# the_ties.net
KiCad netlist of a schematic drawn in EasyEDA Pro
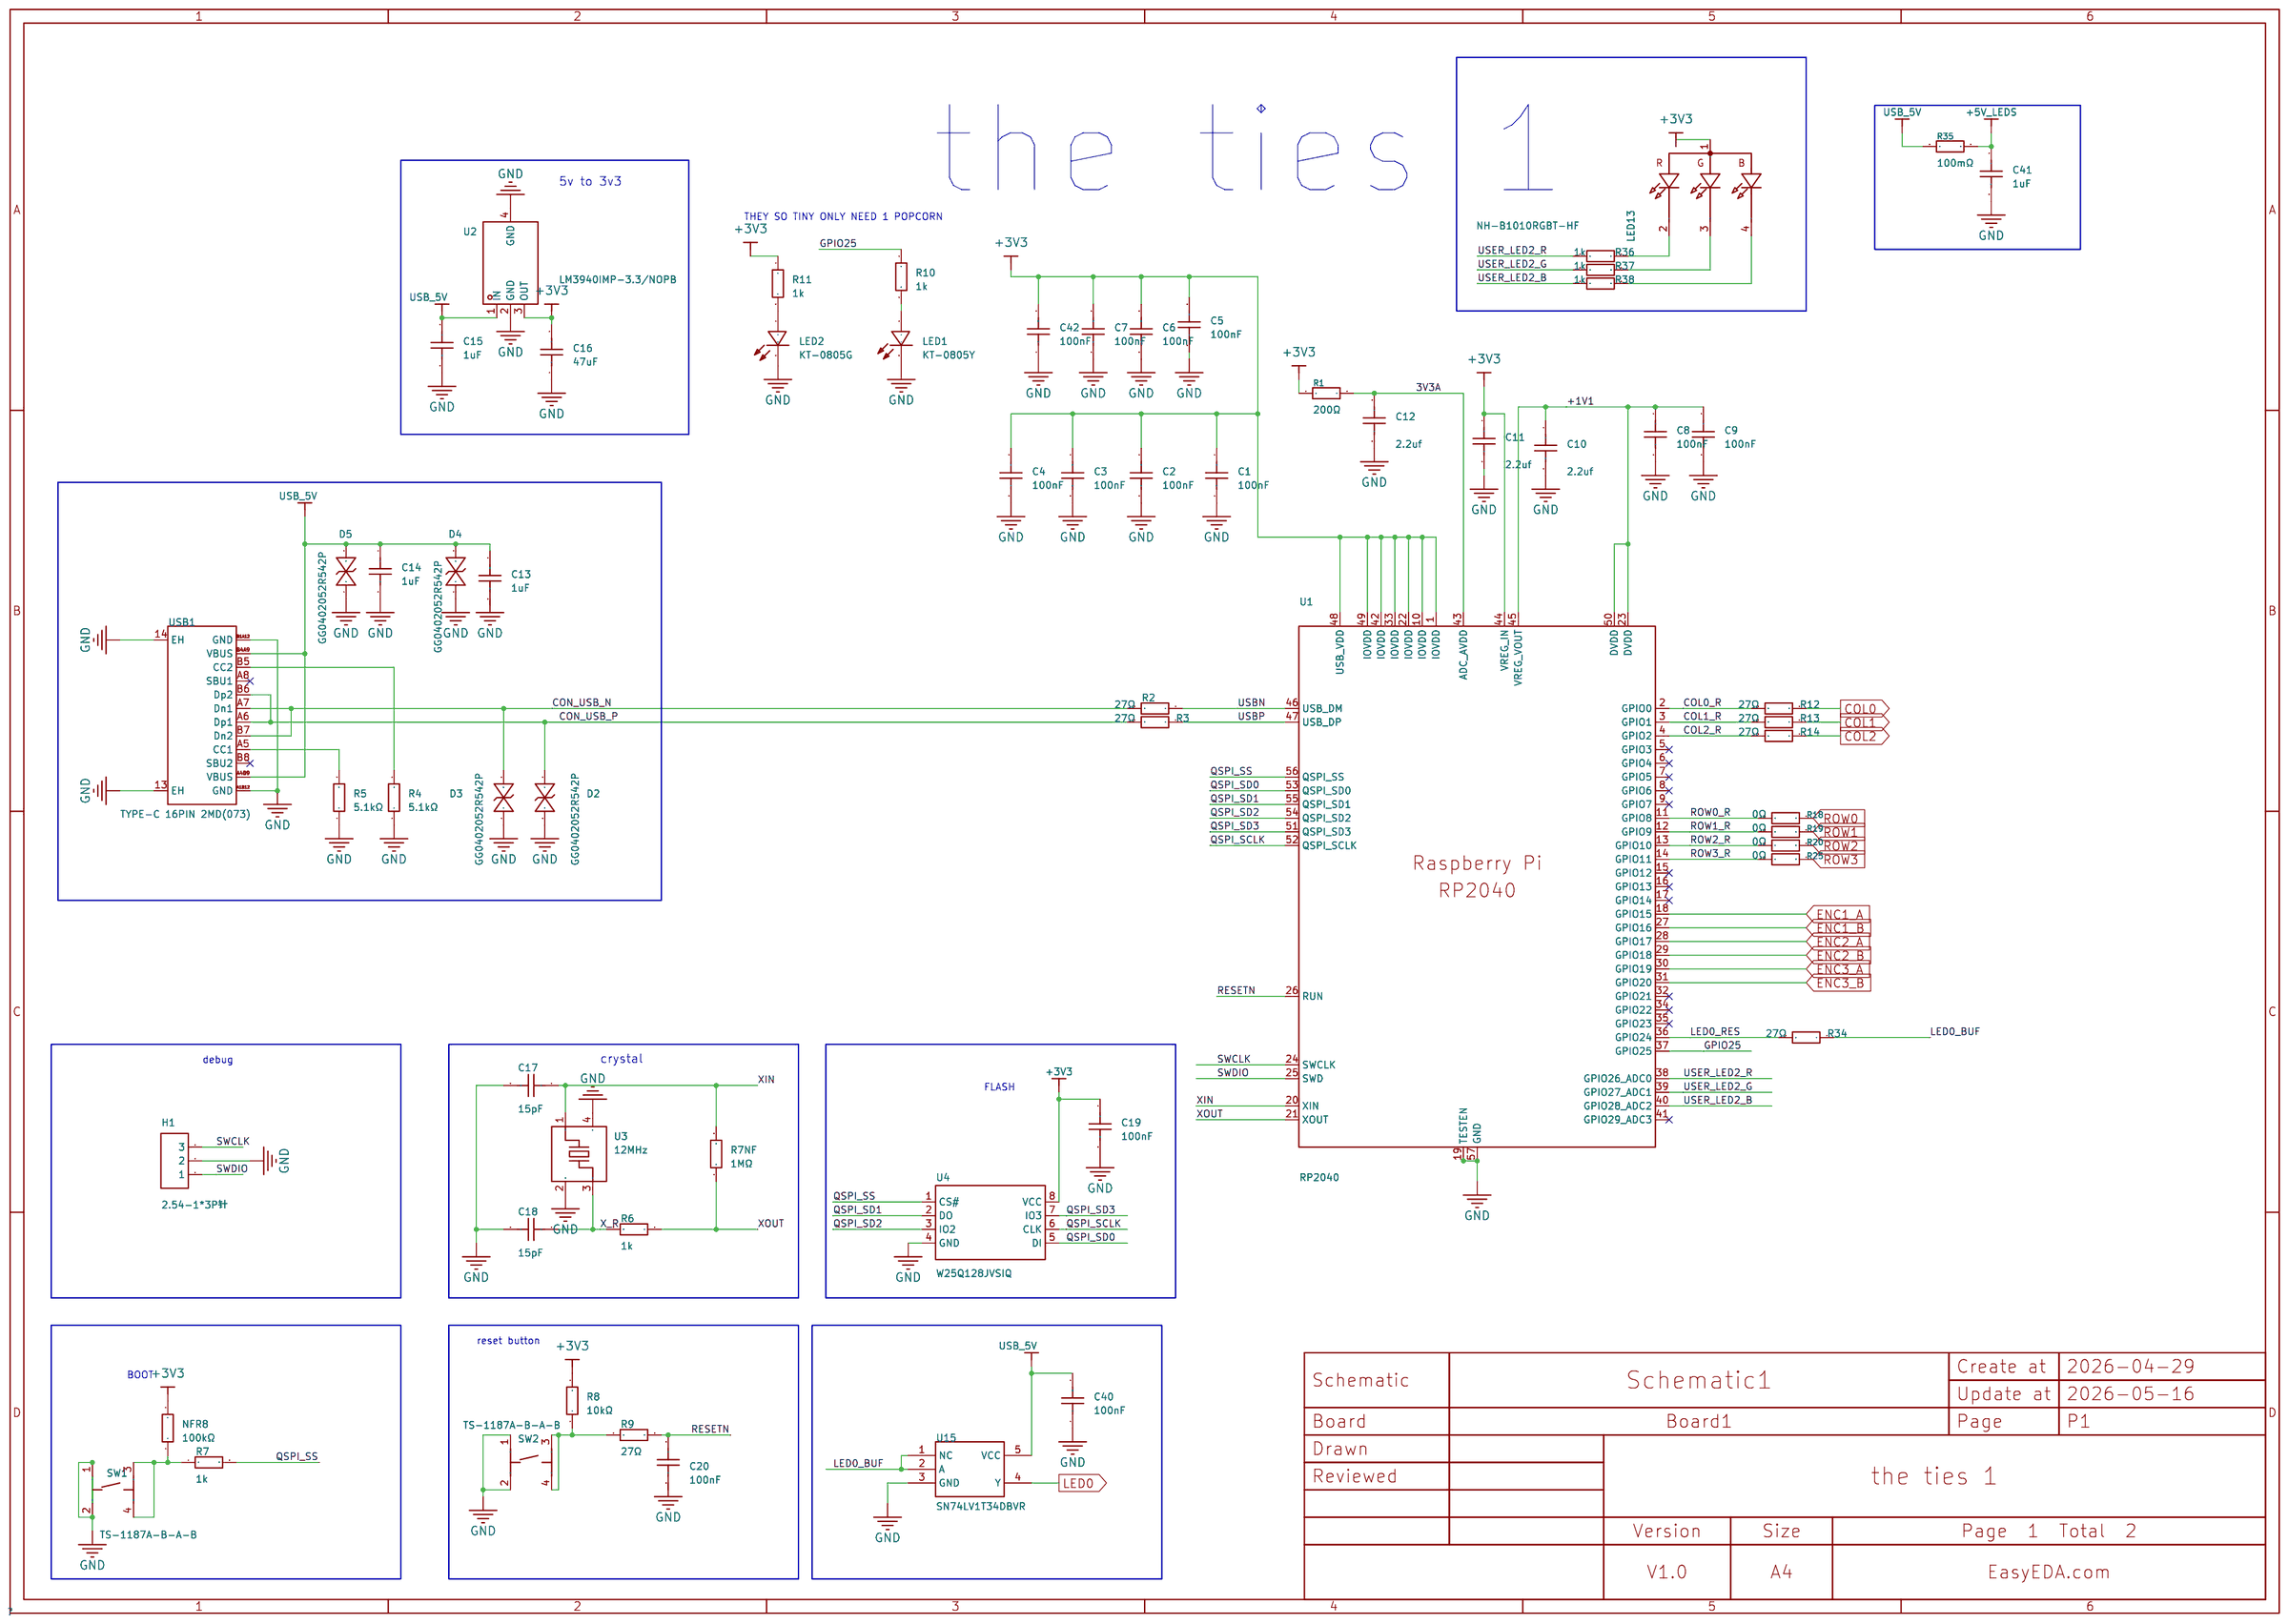
[diagram p0: P1]
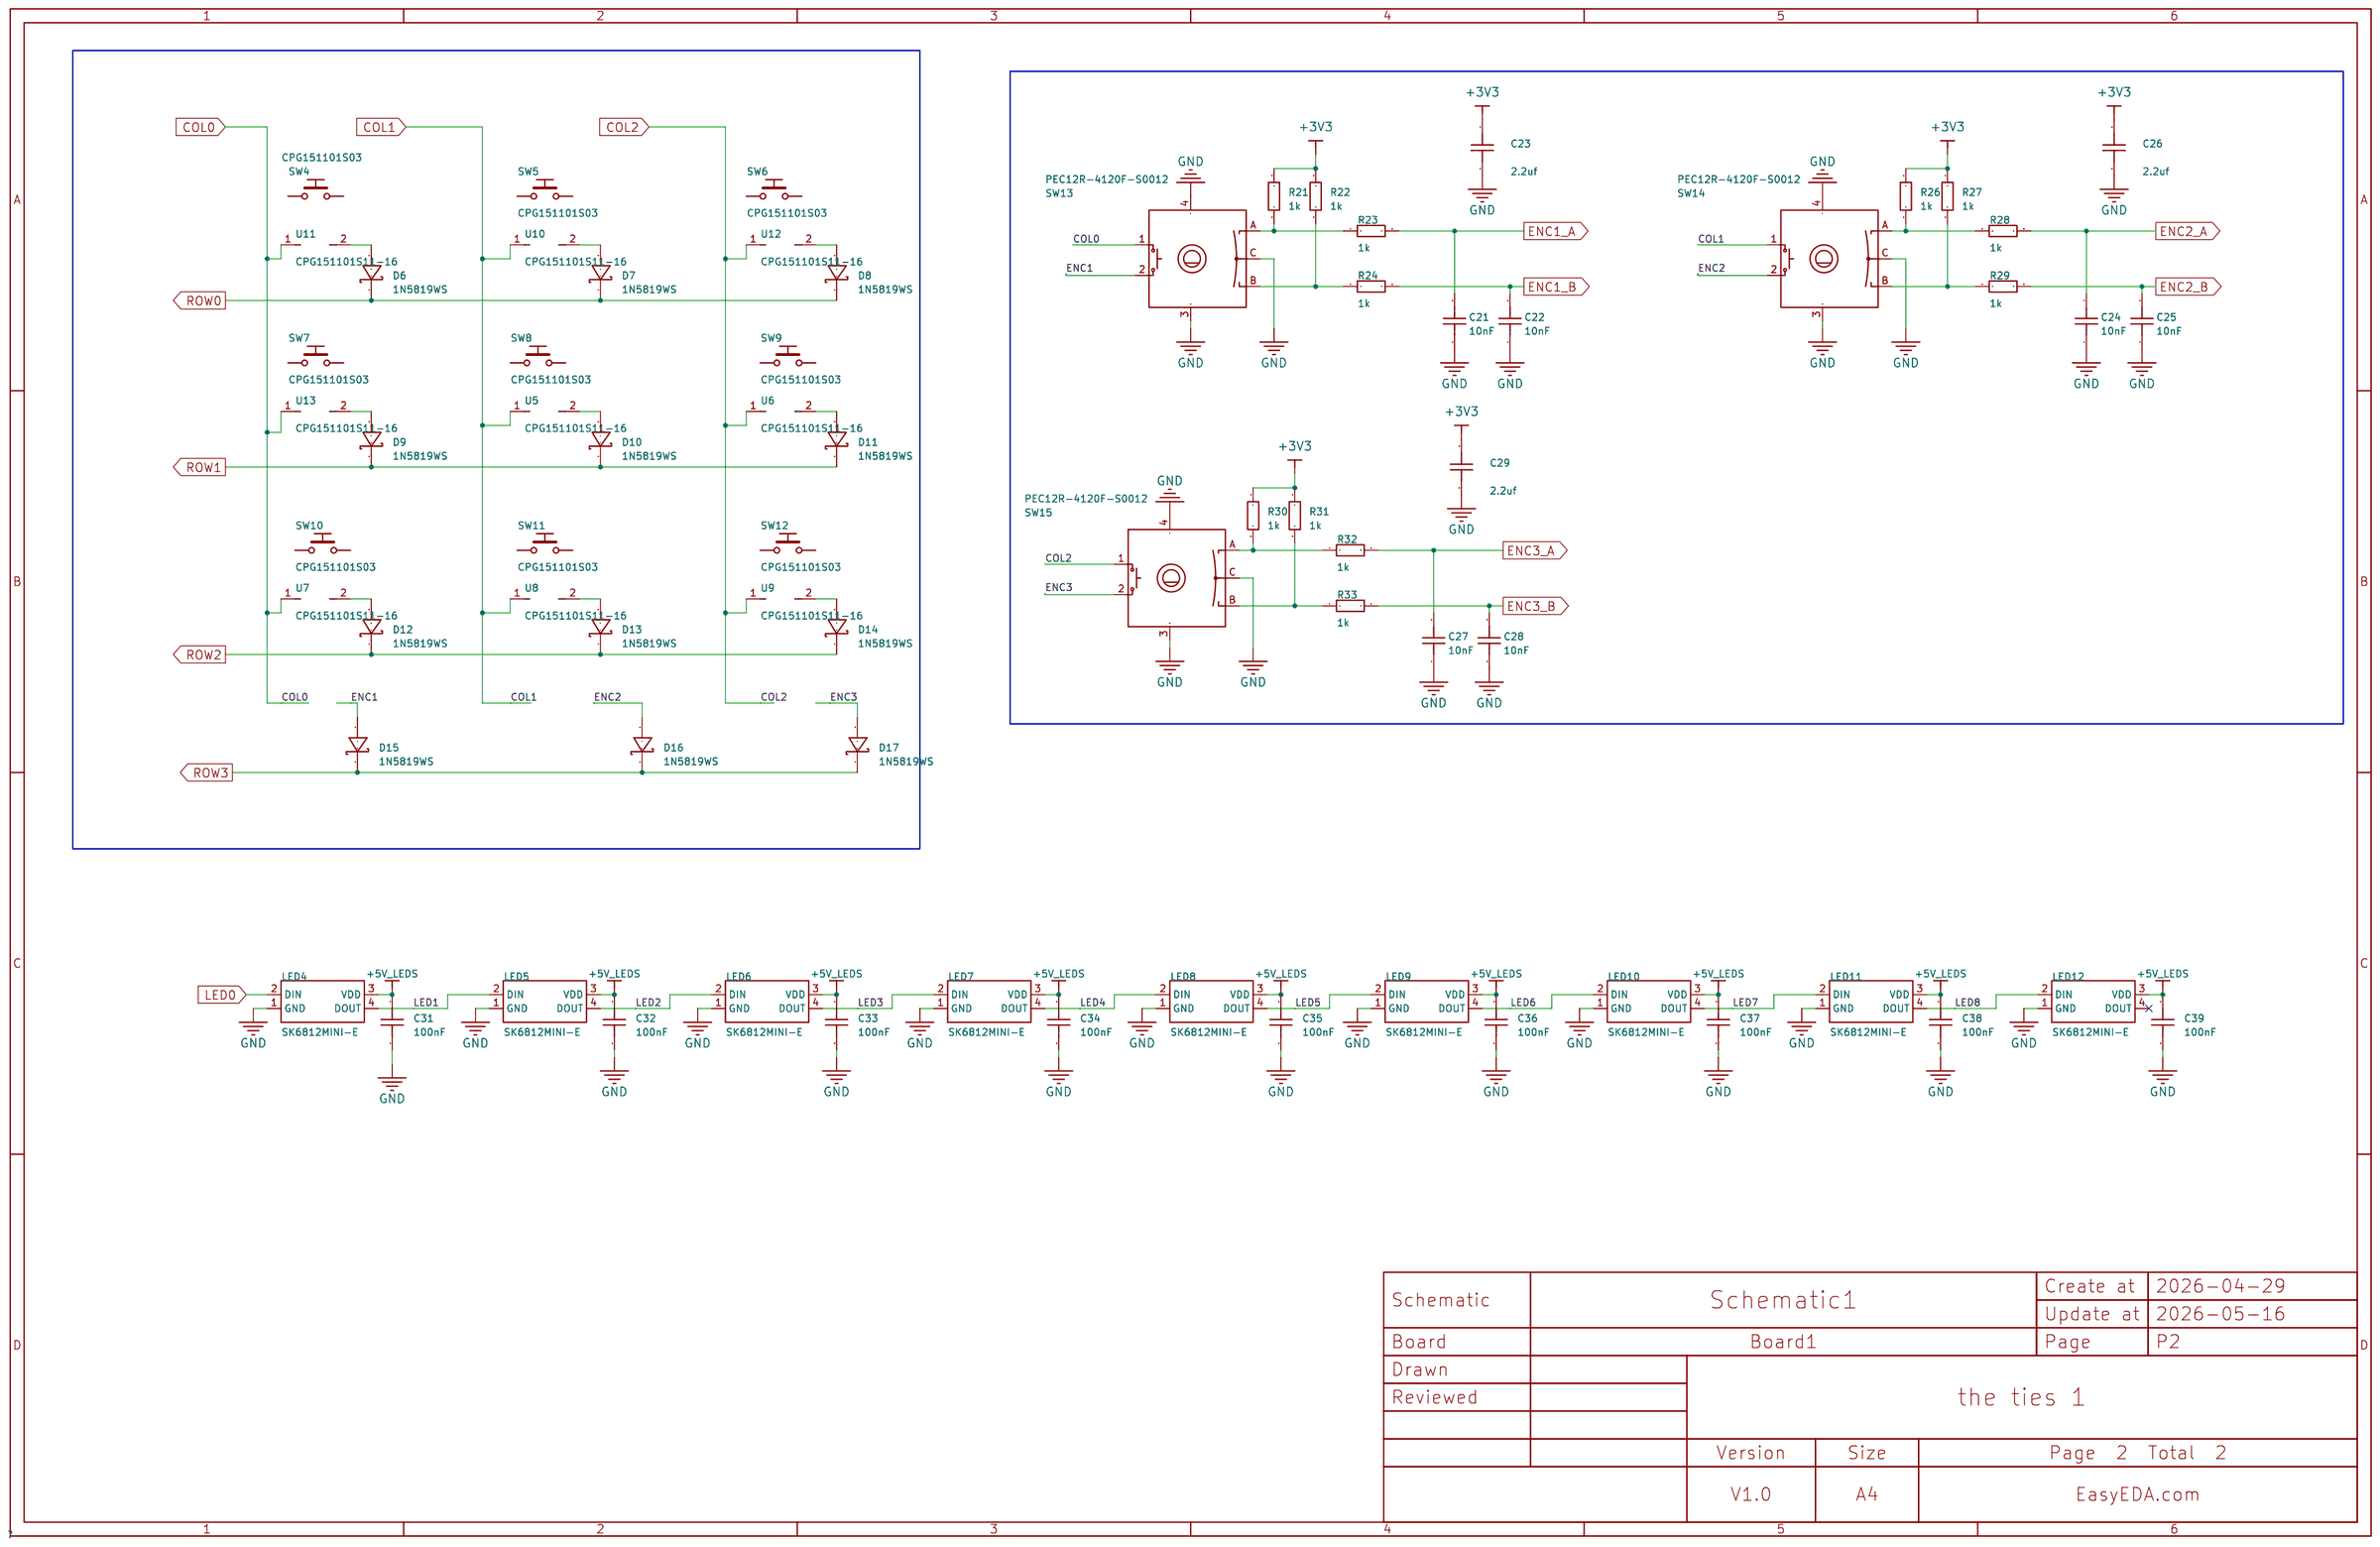
[diagram p1: P2]

(export (version "E")
  (design (tool "Eeschema 10.0.6"))
  (components
    (comp (ref "C1")
      (value "100nF")
      (footprint "easyedapro:C0603")
      (libsource (lib "easyedapro") (part "CAP"))
    )
    (comp (ref "C2")
      (value "100nF")
      (footprint "easyedapro:C0603")
      (libsource (lib "easyedapro") (part "CAP"))
    )
    (comp (ref "C3")
      (value "100nF")
      (footprint "easyedapro:C0603")
      (libsource (lib "easyedapro") (part "CAP"))
    )
    (comp (ref "C4")
      (value "100nF")
      (footprint "easyedapro:C0603")
      (libsource (lib "easyedapro") (part "CAP"))
    )
    (comp (ref "C5")
      (value "100nF")
      (footprint "easyedapro:C0603")
      (libsource (lib "easyedapro") (part "CAP"))
    )
    (comp (ref "C6")
      (value "100nF")
      (footprint "easyedapro:C0603")
      (libsource (lib "easyedapro") (part "CAP"))
    )
    (comp (ref "C7")
      (value "100nF")
      (footprint "easyedapro:C0603")
      (libsource (lib "easyedapro") (part "CAP"))
    )
    (comp (ref "C8")
      (value "100nF")
      (footprint "easyedapro:C0603")
      (libsource (lib "easyedapro") (part "CAP"))
    )
    (comp (ref "C9")
      (value "100nF")
      (footprint "easyedapro:C0603")
      (libsource (lib "easyedapro") (part "CAP"))
    )
    (comp (ref "C10")
      (value "2.2uf")
      (footprint "easyedapro:C0603")
      (libsource (lib "easyedapro") (part "CAP"))
    )
    (comp (ref "C11")
      (value "2.2uf")
      (footprint "easyedapro:C0603")
      (libsource (lib "easyedapro") (part "CAP"))
    )
    (comp (ref "C12")
      (value "2.2uf")
      (footprint "easyedapro:C0603")
      (libsource (lib "easyedapro") (part "CAP"))
    )
    (comp (ref "C13")
      (value "1uF")
      (footprint "easyedapro:C0603")
      (libsource (lib "easyedapro") (part "CAP"))
    )
    (comp (ref "C14")
      (value "1uF")
      (footprint "easyedapro:C0603")
      (libsource (lib "easyedapro") (part "CAP"))
    )
    (comp (ref "C15")
      (value "1uF")
      (footprint "easyedapro:C0603")
      (libsource (lib "easyedapro") (part "CAP"))
    )
    (comp (ref "C16")
      (value "47uF")
      (footprint "easyedapro:C1206")
      (fields
        (field (name "Manufacturer Part") "CL31A476MPHNNNE")
        (field (name "Manufacturer") "SAMSUNG(三星)")
      )
      (libsource (lib "easyedapro") (part "CL31A476MPHNNNE"))
    )
    (comp (ref "C17")
      (value "15pF")
      (footprint "easyedapro:C0402")
      (fields
        (field (name "Manufacturer Part") "CL05C150JB5NNNC")
        (field (name "Manufacturer") "SAMSUNG(三星)")
      )
      (libsource (lib "easyedapro") (part "CL05C150JB5NNNC"))
    )
    (comp (ref "C18")
      (value "15pF")
      (footprint "easyedapro:C0402")
      (fields
        (field (name "Manufacturer Part") "CL05C150JB5NNNC")
        (field (name "Manufacturer") "SAMSUNG(三星)")
      )
      (libsource (lib "easyedapro") (part "CL05C150JB5NNNC"))
    )
    (comp (ref "C19")
      (value "100nF")
      (footprint "easyedapro:C0603")
      (libsource (lib "easyedapro") (part "CAP"))
    )
    (comp (ref "C20")
      (value "100nF")
      (footprint "easyedapro:C0603")
      (libsource (lib "easyedapro") (part "CAP"))
    )
    (comp (ref "C40")
      (value "100nF")
      (footprint "easyedapro:C0603")
      (libsource (lib "easyedapro") (part "CAP"))
    )
    (comp (ref "C41")
      (value "1uF")
      (footprint "easyedapro:C0603")
      (libsource (lib "easyedapro") (part "CAP"))
    )
    (comp (ref "C42")
      (value "100nF")
      (footprint "easyedapro:C0603")
      (libsource (lib "easyedapro") (part "CAP"))
    )
    (comp (ref "D2")
      (value "GG0402052R542P")
      (footprint "easyedapro:D0402-BI")
      (fields (field (name "Manufacturer") "Kyocera AVX"))
      (libsource (lib "easyedapro") (part "GG0402052R542P"))
    )
    (comp (ref "D3")
      (value "GG0402052R542P")
      (footprint "easyedapro:D0402-BI")
      (fields (field (name "Manufacturer") "Kyocera AVX"))
      (libsource (lib "easyedapro") (part "GG0402052R542P"))
    )
    (comp (ref "D4")
      (value "GG0402052R542P")
      (footprint "easyedapro:D0402-BI")
      (fields (field (name "Manufacturer") "Kyocera AVX"))
      (libsource (lib "easyedapro") (part "GG0402052R542P"))
    )
    (comp (ref "D5")
      (value "GG0402052R542P")
      (footprint "easyedapro:D0402-BI")
      (fields (field (name "Manufacturer") "Kyocera AVX"))
      (libsource (lib "easyedapro") (part "GG0402052R542P"))
    )
    (comp (ref "H1")
      (value "2.54-1*3P针")
      (footprint "easyedapro:HDR-TH_3P-P2.54-V-M-1")
      (fields (field (name "Manufacturer") "BOOMELE(博穆精密)"))
      (libsource (lib "easyedapro") (part "Header-Male-2.54_1x3"))
    )
    (comp (ref "LED1")
      (value "KT-0805Y")
      (footprint "easyedapro:LED0805-R-RD")
      (fields (field (name "Manufacturer") "KENTO"))
      (libsource (lib "easyedapro") (part "17-21SUYC/TR8"))
    )
    (comp (ref "LED2")
      (value "KT-0805G")
      (footprint "easyedapro:LED0805-R-RD")
      (fields (field (name "Manufacturer") "KENTO"))
      (libsource (lib "easyedapro") (part "0805G (Green)"))
    )
    (comp (ref "LED13")
      (value "NH-B1010RGBT-HF")
      (footprint "easyedapro:LED-ARRAY-SMD_4P-L1.0-W1.0-TR_NH-B1010RGBT")
      (fields (field (name "Manufacturer") "国星光电"))
      (libsource (lib "easyedapro") (part "NH-B1010RGBT-HF-EDIT"))
    )
    (comp (ref "NFR8")
      (value "100kΩ")
      (footprint "easyedapro:R0603")
      (libsource (lib "easyedapro") (part "Res"))
    )
    (comp (ref "R1")
      (value "200Ω")
      (footprint "easyedapro:R0402")
      (fields
        (field (name "Manufacturer Part") "0402WGF2000TCE")
        (field (name "Manufacturer") "UNI-ROYAL(厚声)")
      )
      (libsource (lib "easyedapro") (part "0402WGF2000TCE"))
    )
    (comp (ref "R2")
      (value "27Ω")
      (footprint "easyedapro:R0402")
      (fields
        (field (name "Manufacturer Part") "0402WGF270JTCE")
        (field (name "Manufacturer") "UNI-ROYAL(厚声)")
      )
      (libsource (lib "easyedapro") (part "0402WGF270JTCE"))
    )
    (comp (ref "R3")
      (value "27Ω")
      (footprint "easyedapro:R0402")
      (fields
        (field (name "Manufacturer Part") "0402WGF270JTCE")
        (field (name "Manufacturer") "UNI-ROYAL(厚声)")
      )
      (libsource (lib "easyedapro") (part "0402WGF270JTCE"))
    )
    (comp (ref "R4")
      (value "5.1kΩ")
      (footprint "easyedapro:R0603")
      (libsource (lib "easyedapro") (part "Res"))
    )
    (comp (ref "R5")
      (value "5.1kΩ")
      (footprint "easyedapro:R0603")
      (libsource (lib "easyedapro") (part "Res"))
    )
    (comp (ref "R6") (value "1k") (footprint "easyedapro:R0603") (libsource (lib "easyedapro") (part "Res")))
    (comp (ref "R7") (value "1k") (footprint "easyedapro:R0603") (libsource (lib "easyedapro") (part "Res")))
    (comp (ref "R7NF")
      (value "1MΩ")
      (footprint "easyedapro:R0603")
      (libsource (lib "easyedapro") (part "Res"))
    )
    (comp (ref "R8")
      (value "10kΩ")
      (footprint "easyedapro:R0603")
      (libsource (lib "easyedapro") (part "Res"))
    )
    (comp (ref "R9")
      (value "27Ω")
      (footprint "easyedapro:R0402")
      (fields
        (field (name "Manufacturer Part") "0402WGF270JTCE")
        (field (name "Manufacturer") "UNI-ROYAL(厚声)")
      )
      (libsource (lib "easyedapro") (part "0402WGF270JTCE"))
    )
    (comp (ref "R10") (value "1k") (footprint "easyedapro:R0603") (libsource (lib "easyedapro") (part "Res")))
    (comp (ref "R11") (value "1k") (footprint "easyedapro:R0603") (libsource (lib "easyedapro") (part "Res")))
    (comp (ref "R12")
      (value "27Ω")
      (footprint "easyedapro:R0402")
      (fields
        (field (name "Manufacturer Part") "0402WGF270JTCE")
        (field (name "Manufacturer") "UNI-ROYAL(厚声)")
      )
      (libsource (lib "easyedapro") (part "0402WGF270JTCE"))
    )
    (comp (ref "R13")
      (value "27Ω")
      (footprint "easyedapro:R0402")
      (fields
        (field (name "Manufacturer Part") "0402WGF270JTCE")
        (field (name "Manufacturer") "UNI-ROYAL(厚声)")
      )
      (libsource (lib "easyedapro") (part "0402WGF270JTCE"))
    )
    (comp (ref "R14")
      (value "27Ω")
      (footprint "easyedapro:R0402")
      (fields
        (field (name "Manufacturer Part") "0402WGF270JTCE")
        (field (name "Manufacturer") "UNI-ROYAL(厚声)")
      )
      (libsource (lib "easyedapro") (part "0402WGF270JTCE"))
    )
    (comp (ref "R18")
      (value "0Ω")
      (footprint "easyedapro:R0402")
      (fields
        (field (name "Manufacturer Part") "0402WGF0000TCE")
        (field (name "Manufacturer") "UNI-ROYAL(厚声)")
      )
      (libsource (lib "easyedapro") (part "0402WGF0000TCE"))
    )
    (comp (ref "R19")
      (value "0Ω")
      (footprint "easyedapro:R0402")
      (fields
        (field (name "Manufacturer Part") "0402WGF0000TCE")
        (field (name "Manufacturer") "UNI-ROYAL(厚声)")
      )
      (libsource (lib "easyedapro") (part "0402WGF0000TCE"))
    )
    (comp (ref "R20")
      (value "0Ω")
      (footprint "easyedapro:R0402")
      (fields
        (field (name "Manufacturer Part") "0402WGF0000TCE")
        (field (name "Manufacturer") "UNI-ROYAL(厚声)")
      )
      (libsource (lib "easyedapro") (part "0402WGF0000TCE"))
    )
    (comp (ref "R25")
      (value "0Ω")
      (footprint "easyedapro:R0402")
      (fields
        (field (name "Manufacturer Part") "0402WGF0000TCE")
        (field (name "Manufacturer") "UNI-ROYAL(厚声)")
      )
      (libsource (lib "easyedapro") (part "0402WGF0000TCE"))
    )
    (comp (ref "R34")
      (value "27Ω")
      (footprint "easyedapro:R0402")
      (fields
        (field (name "Manufacturer Part") "0402WGF270JTCE")
        (field (name "Manufacturer") "UNI-ROYAL(厚声)")
      )
      (libsource (lib "easyedapro") (part "0402WGF270JTCE"))
    )
    (comp (ref "R35")
      (value "100mΩ")
      (footprint "easyedapro:R1206")
      (fields
        (field (name "Manufacturer Part") "1206W4F100LT5E")
        (field (name "Manufacturer") "UNI-ROYAL(厚声)")
      )
      (libsource (lib "easyedapro") (part "1206W4F100LT5E"))
    )
    (comp (ref "R36") (value "1k") (footprint "easyedapro:R0603") (libsource (lib "easyedapro") (part "Res")))
    (comp (ref "R37") (value "1k") (footprint "easyedapro:R0603") (libsource (lib "easyedapro") (part "Res")))
    (comp (ref "R38") (value "1k") (footprint "easyedapro:R0603") (libsource (lib "easyedapro") (part "Res")))
    (comp (ref "SW1")
      (value "TS-1187A-B-A-B")
      (footprint "easyedapro:SW-SMD_4P-L5.1-W5.1-P3.70-LS6.5-TL_H1.5")
      (fields (field (name "Manufacturer") "XKB Connection(中国星坤)"))
      (libsource (lib "easyedapro") (part "TS-1187A-B-A-B"))
    )
    (comp (ref "SW2")
      (value "TS-1187A-B-A-B")
      (footprint "easyedapro:SW-SMD_4P-L5.1-W5.1-P3.70-LS6.5-TL_H1.5")
      (fields (field (name "Manufacturer") "XKB Connection(中国星坤)"))
      (libsource (lib "easyedapro") (part "TS-1187A-B-A-B"))
    )
    (comp (ref "U1")
      (value "RP2040")
      (footprint "easyedapro:LQFN-56_L7.0-W7.0-P0.4-EP")
      (fields (field (name "Manufacturer") "Raspberry Pi(树莓派)"))
      (libsource (lib "easyedapro") (part "RP2040_C2040_Rf_1"))
    )
    (comp (ref "U2")
      (value "LM3940IMP-3.3/NOPB")
      (footprint "easyedapro:SOT-223_L6.5-W3.5-P2.30-LS7.0-BR")
      (fields (field (name "Manufacturer") "TI(德州仪器)"))
      (libsource (lib "easyedapro") (part "LM3940IMP-3.3/NOPB"))
    )
    (comp (ref "U3")
      (value "12MHz")
      (footprint "easyedapro:CRYSTAL-SMD_4P-L3.2-W2.5-BL")
      (fields (field (name "Manufacturer Part") "ABM8-272-T3") (field (name "Manufacturer") "ABRACON"))
      (libsource (lib "easyedapro") (part "ABM8-272-T3_C20625731"))
    )
    (comp (ref "U4")
      (value "W25Q128JVSIQ")
      (footprint "easyedapro:SOIC-8_L5.3-W5.3-P1.27-LS8.0-BL")
      (fields (field (name "Manufacturer") "Winbond(华邦)"))
      (libsource (lib "easyedapro") (part "W25Q128JVSIQTR"))
    )
    (comp (ref "U15")
      (value "SN74LV1T34DBVR")
      (footprint "easyedapro:SOT-23-5_L2.9-W1.6-P0.95-LS2.8-BR")
      (fields (field (name "Manufacturer") "TI(德州仪器)"))
      (libsource (lib "easyedapro") (part "SN74LV1T34DBVR edit"))
    )
    (comp (ref "USB1")
      (value "TYPE-C 16PIN 2MD(073)")
      (footprint "easyedapro:USB-C-SMD_TYPE-C-16PIN-2MD-073")
      (fields (field (name "Manufacturer") "SHOU HAN(首韩)"))
      (libsource (lib "easyedapro") (part "TYPE-C 16PIN 2MD(073)"))
    )
    (comp (ref "C21")
      (value "10nF")
      (footprint "easyedapro:C0603")
      (libsource (lib "easyedapro") (part "CAP"))
    )
    (comp (ref "C22")
      (value "10nF")
      (footprint "easyedapro:C0603")
      (libsource (lib "easyedapro") (part "CAP"))
    )
    (comp (ref "C23")
      (value "2.2uf")
      (footprint "easyedapro:C0603")
      (libsource (lib "easyedapro") (part "CAP"))
    )
    (comp (ref "C24")
      (value "10nF")
      (footprint "easyedapro:C0603")
      (libsource (lib "easyedapro") (part "CAP"))
    )
    (comp (ref "C25")
      (value "10nF")
      (footprint "easyedapro:C0603")
      (libsource (lib "easyedapro") (part "CAP"))
    )
    (comp (ref "C26")
      (value "2.2uf")
      (footprint "easyedapro:C0603")
      (libsource (lib "easyedapro") (part "CAP"))
    )
    (comp (ref "C27")
      (value "10nF")
      (footprint "easyedapro:C0603")
      (libsource (lib "easyedapro") (part "CAP"))
    )
    (comp (ref "C28")
      (value "10nF")
      (footprint "easyedapro:C0603")
      (libsource (lib "easyedapro") (part "CAP"))
    )
    (comp (ref "C29")
      (value "2.2uf")
      (footprint "easyedapro:C0603")
      (libsource (lib "easyedapro") (part "CAP"))
    )
    (comp (ref "C31")
      (value "100nF")
      (footprint "easyedapro:C0603")
      (libsource (lib "easyedapro") (part "CAP"))
    )
    (comp (ref "C32")
      (value "100nF")
      (footprint "easyedapro:C0603")
      (libsource (lib "easyedapro") (part "CAP"))
    )
    (comp (ref "C33")
      (value "100nF")
      (footprint "easyedapro:C0603")
      (libsource (lib "easyedapro") (part "CAP"))
    )
    (comp (ref "C34")
      (value "100nF")
      (footprint "easyedapro:C0603")
      (libsource (lib "easyedapro") (part "CAP"))
    )
    (comp (ref "C35")
      (value "100nF")
      (footprint "easyedapro:C0603")
      (libsource (lib "easyedapro") (part "CAP"))
    )
    (comp (ref "C36")
      (value "100nF")
      (footprint "easyedapro:C0603")
      (libsource (lib "easyedapro") (part "CAP"))
    )
    (comp (ref "C37")
      (value "100nF")
      (footprint "easyedapro:C0603")
      (libsource (lib "easyedapro") (part "CAP"))
    )
    (comp (ref "C38")
      (value "100nF")
      (footprint "easyedapro:C0603")
      (libsource (lib "easyedapro") (part "CAP"))
    )
    (comp (ref "C39")
      (value "100nF")
      (footprint "easyedapro:C0603")
      (libsource (lib "easyedapro") (part "CAP"))
    )
    (comp (ref "D6")
      (value "1N5819WS")
      (footprint "easyedapro:SOD-323_L1.8-W1.3-LS2.5-RD")
      (fields (field (name "Manufacturer") "Hottech(合科泰)"))
      (libsource (lib "easyedapro") (part "1N5819WS"))
    )
    (comp (ref "D7")
      (value "1N5819WS")
      (footprint "easyedapro:SOD-323_L1.8-W1.3-LS2.5-RD")
      (fields (field (name "Manufacturer") "Hottech(合科泰)"))
      (libsource (lib "easyedapro") (part "1N5819WS"))
    )
    (comp (ref "D8")
      (value "1N5819WS")
      (footprint "easyedapro:SOD-323_L1.8-W1.3-LS2.5-RD")
      (fields (field (name "Manufacturer") "Hottech(合科泰)"))
      (libsource (lib "easyedapro") (part "1N5819WS"))
    )
    (comp (ref "D9")
      (value "1N5819WS")
      (footprint "easyedapro:SOD-323_L1.8-W1.3-LS2.5-RD")
      (fields (field (name "Manufacturer") "Hottech(合科泰)"))
      (libsource (lib "easyedapro") (part "1N5819WS"))
    )
    (comp (ref "D10")
      (value "1N5819WS")
      (footprint "easyedapro:SOD-323_L1.8-W1.3-LS2.5-RD")
      (fields (field (name "Manufacturer") "Hottech(合科泰)"))
      (libsource (lib "easyedapro") (part "1N5819WS"))
    )
    (comp (ref "D11")
      (value "1N5819WS")
      (footprint "easyedapro:SOD-323_L1.8-W1.3-LS2.5-RD")
      (fields (field (name "Manufacturer") "Hottech(合科泰)"))
      (libsource (lib "easyedapro") (part "1N5819WS"))
    )
    (comp (ref "D12")
      (value "1N5819WS")
      (footprint "easyedapro:SOD-323_L1.8-W1.3-LS2.5-RD")
      (fields (field (name "Manufacturer") "Hottech(合科泰)"))
      (libsource (lib "easyedapro") (part "1N5819WS"))
    )
    (comp (ref "D13")
      (value "1N5819WS")
      (footprint "easyedapro:SOD-323_L1.8-W1.3-LS2.5-RD")
      (fields (field (name "Manufacturer") "Hottech(合科泰)"))
      (libsource (lib "easyedapro") (part "1N5819WS"))
    )
    (comp (ref "D14")
      (value "1N5819WS")
      (footprint "easyedapro:SOD-323_L1.8-W1.3-LS2.5-RD")
      (fields (field (name "Manufacturer") "Hottech(合科泰)"))
      (libsource (lib "easyedapro") (part "1N5819WS"))
    )
    (comp (ref "D15")
      (value "1N5819WS")
      (footprint "easyedapro:SOD-323_L1.8-W1.3-LS2.5-RD")
      (fields (field (name "Manufacturer") "Hottech(合科泰)"))
      (libsource (lib "easyedapro") (part "1N5819WS"))
    )
    (comp (ref "D16")
      (value "1N5819WS")
      (footprint "easyedapro:SOD-323_L1.8-W1.3-LS2.5-RD")
      (fields (field (name "Manufacturer") "Hottech(合科泰)"))
      (libsource (lib "easyedapro") (part "1N5819WS"))
    )
    (comp (ref "D17")
      (value "1N5819WS")
      (footprint "easyedapro:SOD-323_L1.8-W1.3-LS2.5-RD")
      (fields (field (name "Manufacturer") "Hottech(合科泰)"))
      (libsource (lib "easyedapro") (part "1N5819WS"))
    )
    (comp (ref "LED4")
      (value "SK6812MINI-E")
      (footprint "easyedapro:LED-SMD_4P-L3.2-W2.8-LS5.9_SK6812MINI-E")
      (fields (field (name "Manufacturer") "欧思科光电"))
      (libsource (lib "easyedapro") (part "SK6812MINI-E_C5149201"))
    )
    (comp (ref "LED5")
      (value "SK6812MINI-E")
      (footprint "easyedapro:LED-SMD_4P-L3.2-W2.8-LS5.9_SK6812MINI-E")
      (fields (field (name "Manufacturer") "欧思科光电"))
      (libsource (lib "easyedapro") (part "SK6812MINI-E_C5149201"))
    )
    (comp (ref "LED6")
      (value "SK6812MINI-E")
      (footprint "easyedapro:LED-SMD_4P-L3.2-W2.8-LS5.9_SK6812MINI-E")
      (fields (field (name "Manufacturer") "欧思科光电"))
      (libsource (lib "easyedapro") (part "SK6812MINI-E_C5149201"))
    )
    (comp (ref "LED7")
      (value "SK6812MINI-E")
      (footprint "easyedapro:LED-SMD_4P-L3.2-W2.8-LS5.9_SK6812MINI-E")
      (fields (field (name "Manufacturer") "欧思科光电"))
      (libsource (lib "easyedapro") (part "SK6812MINI-E_C5149201"))
    )
    (comp (ref "LED8")
      (value "SK6812MINI-E")
      (footprint "easyedapro:LED-SMD_4P-L3.2-W2.8-LS5.9_SK6812MINI-E")
      (fields (field (name "Manufacturer") "欧思科光电"))
      (libsource (lib "easyedapro") (part "SK6812MINI-E_C5149201"))
    )
    (comp (ref "LED9")
      (value "SK6812MINI-E")
      (footprint "easyedapro:LED-SMD_4P-L3.2-W2.8-LS5.9_SK6812MINI-E")
      (fields (field (name "Manufacturer") "欧思科光电"))
      (libsource (lib "easyedapro") (part "SK6812MINI-E_C5149201"))
    )
    (comp (ref "LED10")
      (value "SK6812MINI-E")
      (footprint "easyedapro:LED-SMD_4P-L3.2-W2.8-LS5.9_SK6812MINI-E")
      (fields (field (name "Manufacturer") "欧思科光电"))
      (libsource (lib "easyedapro") (part "SK6812MINI-E_C5149201"))
    )
    (comp (ref "LED11")
      (value "SK6812MINI-E")
      (footprint "easyedapro:LED-SMD_4P-L3.2-W2.8-LS5.9_SK6812MINI-E")
      (fields (field (name "Manufacturer") "欧思科光电"))
      (libsource (lib "easyedapro") (part "SK6812MINI-E_C5149201"))
    )
    (comp (ref "LED12")
      (value "SK6812MINI-E")
      (footprint "easyedapro:LED-SMD_4P-L3.2-W2.8-LS5.9_SK6812MINI-E")
      (fields (field (name "Manufacturer") "欧思科光电"))
      (libsource (lib "easyedapro") (part "SK6812MINI-E_C5149201"))
    )
    (comp (ref "R21") (value "1k") (footprint "easyedapro:R0603") (libsource (lib "easyedapro") (part "Res")))
    (comp (ref "R22") (value "1k") (footprint "easyedapro:R0603") (libsource (lib "easyedapro") (part "Res")))
    (comp (ref "R23") (value "1k") (footprint "easyedapro:R0603") (libsource (lib "easyedapro") (part "Res")))
    (comp (ref "R24") (value "1k") (footprint "easyedapro:R0603") (libsource (lib "easyedapro") (part "Res")))
    (comp (ref "R26") (value "1k") (footprint "easyedapro:R0603") (libsource (lib "easyedapro") (part "Res")))
    (comp (ref "R27") (value "1k") (footprint "easyedapro:R0603") (libsource (lib "easyedapro") (part "Res")))
    (comp (ref "R28") (value "1k") (footprint "easyedapro:R0603") (libsource (lib "easyedapro") (part "Res")))
    (comp (ref "R29") (value "1k") (footprint "easyedapro:R0603") (libsource (lib "easyedapro") (part "Res")))
    (comp (ref "R30") (value "1k") (footprint "easyedapro:R0603") (libsource (lib "easyedapro") (part "Res")))
    (comp (ref "R31") (value "1k") (footprint "easyedapro:R0603") (libsource (lib "easyedapro") (part "Res")))
    (comp (ref "R32") (value "1k") (footprint "easyedapro:R0603") (libsource (lib "easyedapro") (part "Res")))
    (comp (ref "R33") (value "1k") (footprint "easyedapro:R0603") (libsource (lib "easyedapro") (part "Res")))
    (comp (ref "SW4")
      (value "CPG151101S03")
      (footprint "easyedapro:KEY-TH_CPG1511F01S0X")
      (fields (field (name "Manufacturer") "Kailh(凯华)"))
      (libsource (lib "easyedapro") (part "CPG151101S03 edit"))
    )
    (comp (ref "SW5")
      (value "CPG151101S03")
      (footprint "easyedapro:KEY-TH_CPG1511F01S0X")
      (fields (field (name "Manufacturer") "Kailh(凯华)"))
      (libsource (lib "easyedapro") (part "CPG151101S03 edit"))
    )
    (comp (ref "SW6")
      (value "CPG151101S03")
      (footprint "easyedapro:KEY-TH_CPG1511F01S0X")
      (fields (field (name "Manufacturer") "Kailh(凯华)"))
      (libsource (lib "easyedapro") (part "CPG151101S03 edit"))
    )
    (comp (ref "SW7")
      (value "CPG151101S03")
      (footprint "easyedapro:KEY-TH_CPG1511F01S0X")
      (fields (field (name "Manufacturer") "Kailh(凯华)"))
      (libsource (lib "easyedapro") (part "CPG151101S03 edit"))
    )
    (comp (ref "SW8")
      (value "CPG151101S03")
      (footprint "easyedapro:KEY-TH_CPG1511F01S0X")
      (fields (field (name "Manufacturer") "Kailh(凯华)"))
      (libsource (lib "easyedapro") (part "CPG151101S03 edit"))
    )
    (comp (ref "SW9")
      (value "CPG151101S03")
      (footprint "easyedapro:KEY-TH_CPG1511F01S0X")
      (fields (field (name "Manufacturer") "Kailh(凯华)"))
      (libsource (lib "easyedapro") (part "CPG151101S03 edit"))
    )
    (comp (ref "SW10")
      (value "CPG151101S03")
      (footprint "easyedapro:KEY-TH_CPG1511F01S0X")
      (fields (field (name "Manufacturer") "Kailh(凯华)"))
      (libsource (lib "easyedapro") (part "CPG151101S03 edit"))
    )
    (comp (ref "SW11")
      (value "CPG151101S03")
      (footprint "easyedapro:KEY-TH_CPG1511F01S0X")
      (fields (field (name "Manufacturer") "Kailh(凯华)"))
      (libsource (lib "easyedapro") (part "CPG151101S03 edit"))
    )
    (comp (ref "SW12")
      (value "CPG151101S03")
      (footprint "easyedapro:KEY-TH_CPG1511F01S0X")
      (fields (field (name "Manufacturer") "Kailh(凯华)"))
      (libsource (lib "easyedapro") (part "CPG151101S03 edit"))
    )
    (comp (ref "SW13")
      (value "PEC12R-4120F-S0012")
      (footprint "easyedapro:SW-TH_PEC12R-4120F-S0012")
      (fields (field (name "Manufacturer") "BOURNS"))
      (libsource (lib "easyedapro") (part "PEC12R-4120F-S0012 edit"))
    )
    (comp (ref "SW14")
      (value "PEC12R-4120F-S0012")
      (footprint "easyedapro:SW-TH_PEC12R-4120F-S0012")
      (fields (field (name "Manufacturer") "BOURNS"))
      (libsource (lib "easyedapro") (part "PEC12R-4120F-S0012 edit"))
    )
    (comp (ref "SW15")
      (value "PEC12R-4120F-S0012")
      (footprint "easyedapro:SW-TH_PEC12R-4120F-S0012")
      (fields (field (name "Manufacturer") "BOURNS"))
      (libsource (lib "easyedapro") (part "PEC12R-4120F-S0012 edit"))
    )
    (comp (ref "U5")
      (value "CPG151101S11-16")
      (footprint "easyedapro:SMD_KEYBOARD-SW")
      (fields (field (name "Manufacturer") "Kailh(凯华)"))
      (libsource (lib "easyedapro") (part "CPG151101S11-16-asas"))
    )
    (comp (ref "U6")
      (value "CPG151101S11-16")
      (footprint "easyedapro:SMD_KEYBOARD-SW")
      (fields (field (name "Manufacturer") "Kailh(凯华)"))
      (libsource (lib "easyedapro") (part "CPG151101S11-16-asas"))
    )
    (comp (ref "U7")
      (value "CPG151101S11-16")
      (footprint "easyedapro:SMD_KEYBOARD-SW")
      (fields (field (name "Manufacturer") "Kailh(凯华)"))
      (libsource (lib "easyedapro") (part "CPG151101S11-16-asas"))
    )
    (comp (ref "U8")
      (value "CPG151101S11-16")
      (footprint "easyedapro:SMD_KEYBOARD-SW")
      (fields (field (name "Manufacturer") "Kailh(凯华)"))
      (libsource (lib "easyedapro") (part "CPG151101S11-16-asas"))
    )
    (comp (ref "U9")
      (value "CPG151101S11-16")
      (footprint "easyedapro:SMD_KEYBOARD-SW")
      (fields (field (name "Manufacturer") "Kailh(凯华)"))
      (libsource (lib "easyedapro") (part "CPG151101S11-16-asas"))
    )
    (comp (ref "U10")
      (value "CPG151101S11-16")
      (footprint "easyedapro:SMD_KEYBOARD-SW")
      (fields (field (name "Manufacturer") "Kailh(凯华)"))
      (libsource (lib "easyedapro") (part "CPG151101S11-16-asas"))
    )
    (comp (ref "U11")
      (value "CPG151101S11-16")
      (footprint "easyedapro:SMD_KEYBOARD-SW")
      (fields (field (name "Manufacturer") "Kailh(凯华)"))
      (libsource (lib "easyedapro") (part "CPG151101S11-16-asas"))
    )
    (comp (ref "U12")
      (value "CPG151101S11-16")
      (footprint "easyedapro:SMD_KEYBOARD-SW")
      (fields (field (name "Manufacturer") "Kailh(凯华)"))
      (libsource (lib "easyedapro") (part "CPG151101S11-16-asas"))
    )
    (comp (ref "U13")
      (value "CPG151101S11-16")
      (footprint "easyedapro:SMD_KEYBOARD-SW")
      (fields (field (name "Manufacturer") "Kailh(凯华)"))
      (libsource (lib "easyedapro") (part "CPG151101S11-16-asas"))
    )
  )
  (nets
    (net (code "1") (name "+1V1") (class "Default")
      (node (ref "C10") (pin "1") (pinfunction "1_1") (pintype "input"))
      (node (ref "C8") (pin "1") (pinfunction "1_1") (pintype "input"))
      (node (ref "C9") (pin "1") (pinfunction "1_1") (pintype "input"))
      (node (ref "U1") (pin "23") (pinfunction "DVDD_23") (pintype "bidirectional"))
      (node (ref "U1") (pin "45") (pinfunction "VREG_VOUT_45") (pintype "bidirectional"))
      (node (ref "U1") (pin "50") (pinfunction "DVDD_50") (pintype "bidirectional"))
    )
    (net (code "2") (name "+3V3") (class "Default")
      (node (ref "C1") (pin "1") (pinfunction "1_1") (pintype "input"))
      (node (ref "C11") (pin "1") (pinfunction "1_1") (pintype "input"))
      (node (ref "C16") (pin "2") (pinfunction "2_2") (pintype "unspecified"))
      (node (ref "C19") (pin "1") (pinfunction "1_1") (pintype "input"))
      (node (ref "C2") (pin "1") (pinfunction "1_1") (pintype "input"))
      (node (ref "C23") (pin "1") (pinfunction "1_1") (pintype "input"))
      (node (ref "C26") (pin "1") (pinfunction "1_1") (pintype "input"))
      (node (ref "C29") (pin "1") (pinfunction "1_1") (pintype "input"))
      (node (ref "C3") (pin "1") (pinfunction "1_1") (pintype "input"))
      (node (ref "C4") (pin "1") (pinfunction "1_1") (pintype "input"))
      (node (ref "C42") (pin "2") (pinfunction "2_2") (pintype "input"))
      (node (ref "C5") (pin "2") (pinfunction "2_2") (pintype "input"))
      (node (ref "C6") (pin "2") (pinfunction "2_2") (pintype "input"))
      (node (ref "C7") (pin "2") (pinfunction "2_2") (pintype "input"))
      (node (ref "LED13") (pin "1") (pinfunction "+_1") (pintype "unspecified"))
      (node (ref "NFR8") (pin "2") (pinfunction "2_2") (pintype "input"))
      (node (ref "R1") (pin "1") (pinfunction "1_1") (pintype "input"))
      (node (ref "R11") (pin "1") (pinfunction "1_1") (pintype "input"))
      (node (ref "R21") (pin "1") (pinfunction "1_1") (pintype "input"))
      (node (ref "R22") (pin "1") (pinfunction "1_1") (pintype "input"))
      (node (ref "R26") (pin "1") (pinfunction "1_1") (pintype "input"))
      (node (ref "R27") (pin "1") (pinfunction "1_1") (pintype "input"))
      (node (ref "R30") (pin "1") (pinfunction "1_1") (pintype "input"))
      (node (ref "R31") (pin "1") (pinfunction "1_1") (pintype "input"))
      (node (ref "R8") (pin "2") (pinfunction "2_2") (pintype "input"))
      (node (ref "U1") (pin "1") (pinfunction "IOVDD_1") (pintype "bidirectional"))
      (node (ref "U1") (pin "10") (pinfunction "IOVDD_10") (pintype "bidirectional"))
      (node (ref "U1") (pin "22") (pinfunction "IOVDD_22") (pintype "bidirectional"))
      (node (ref "U1") (pin "33") (pinfunction "IOVDD_33") (pintype "bidirectional"))
      (node (ref "U1") (pin "42") (pinfunction "IOVDD_42") (pintype "bidirectional"))
      (node (ref "U1") (pin "44") (pinfunction "VREG_IN_44") (pintype "bidirectional"))
      (node (ref "U1") (pin "48") (pinfunction "USB_VDD_48") (pintype "bidirectional"))
      (node (ref "U1") (pin "49") (pinfunction "IOVDD_49") (pintype "bidirectional"))
      (node (ref "U2") (pin "3") (pinfunction "OUT_3") (pintype "unspecified"))
      (node (ref "U4") (pin "8") (pinfunction "VCC_8") (pintype "unspecified"))
    )
    (net (code "3") (name "+5V_LEDS") (class "Default")
      (node (ref "C31") (pin "1") (pinfunction "1_1") (pintype "input"))
      (node (ref "C32") (pin "1") (pinfunction "1_1") (pintype "input"))
      (node (ref "C33") (pin "1") (pinfunction "1_1") (pintype "input"))
      (node (ref "C34") (pin "1") (pinfunction "1_1") (pintype "input"))
      (node (ref "C35") (pin "1") (pinfunction "1_1") (pintype "input"))
      (node (ref "C36") (pin "1") (pinfunction "1_1") (pintype "input"))
      (node (ref "C37") (pin "1") (pinfunction "1_1") (pintype "input"))
      (node (ref "C38") (pin "1") (pinfunction "1_1") (pintype "input"))
      (node (ref "C39") (pin "1") (pinfunction "1_1") (pintype "input"))
      (node (ref "C41") (pin "1") (pinfunction "1_1") (pintype "input"))
      (node (ref "LED10") (pin "3") (pinfunction "VDD_3") (pintype "unspecified"))
      (node (ref "LED11") (pin "3") (pinfunction "VDD_3") (pintype "unspecified"))
      (node (ref "LED12") (pin "3") (pinfunction "VDD_3") (pintype "unspecified"))
      (node (ref "LED4") (pin "3") (pinfunction "VDD_3") (pintype "unspecified"))
      (node (ref "LED5") (pin "3") (pinfunction "VDD_3") (pintype "unspecified"))
      (node (ref "LED6") (pin "3") (pinfunction "VDD_3") (pintype "unspecified"))
      (node (ref "LED7") (pin "3") (pinfunction "VDD_3") (pintype "unspecified"))
      (node (ref "LED8") (pin "3") (pinfunction "VDD_3") (pintype "unspecified"))
      (node (ref "LED9") (pin "3") (pinfunction "VDD_3") (pintype "unspecified"))
      (node (ref "R35") (pin "2") (pinfunction "2_2") (pintype "input"))
    )
    (net (code "4") (name "3V3A") (class "Default")
      (node (ref "C12") (pin "1") (pinfunction "1_1") (pintype "input"))
      (node (ref "R1") (pin "2") (pinfunction "2_2") (pintype "input"))
      (node (ref "U1") (pin "43") (pinfunction "ADC_AVDD_43") (pintype "bidirectional"))
    )
    (net (code "5") (name "COL0") (class "Default")
      (node (ref "R12") (pin "1") (pinfunction "1_1") (pintype "input"))
      (node (ref "SW13") (pin "1") (pinfunction "1_1") (pintype "unspecified"))
      (node (ref "U11") (pin "1") (pinfunction "1_1") (pintype "input"))
      (node (ref "U13") (pin "1") (pinfunction "1_1") (pintype "input"))
      (node (ref "U7") (pin "1") (pinfunction "1_1") (pintype "input"))
    )
    (net (code "6") (name "COL0_R") (class "Default")
      (node (ref "R12") (pin "2") (pinfunction "2_2") (pintype "input"))
      (node (ref "U1") (pin "2") (pinfunction "GPIO0_2") (pintype "bidirectional"))
    )
    (net (code "7") (name "COL1") (class "Default")
      (node (ref "R13") (pin "1") (pinfunction "1_1") (pintype "input"))
      (node (ref "SW14") (pin "1") (pinfunction "1_1") (pintype "unspecified"))
      (node (ref "U10") (pin "1") (pinfunction "1_1") (pintype "input"))
      (node (ref "U5") (pin "1") (pinfunction "1_1") (pintype "input"))
      (node (ref "U8") (pin "1") (pinfunction "1_1") (pintype "input"))
    )
    (net (code "8") (name "COL1_R") (class "Default")
      (node (ref "R13") (pin "2") (pinfunction "2_2") (pintype "input"))
      (node (ref "U1") (pin "3") (pinfunction "GPIO1_3") (pintype "bidirectional"))
    )
    (net (code "9") (name "COL2") (class "Default")
      (node (ref "R14") (pin "1") (pinfunction "1_1") (pintype "input"))
      (node (ref "SW15") (pin "1") (pinfunction "1_1") (pintype "unspecified"))
      (node (ref "U12") (pin "1") (pinfunction "1_1") (pintype "input"))
      (node (ref "U6") (pin "1") (pinfunction "1_1") (pintype "input"))
      (node (ref "U9") (pin "1") (pinfunction "1_1") (pintype "input"))
    )
    (net (code "10") (name "COL2_R") (class "Default")
      (node (ref "R14") (pin "2") (pinfunction "2_2") (pintype "input"))
      (node (ref "U1") (pin "4") (pinfunction "GPIO2_4") (pintype "bidirectional"))
    )
    (net (code "11") (name "CON_USB_N") (class "Default")
      (node (ref "D3") (pin "2") (pinfunction "2_2") (pintype "unspecified"))
      (node (ref "R2") (pin "2") (pinfunction "2_2") (pintype "input"))
      (node (ref "USB1") (pin "A7") (pinfunction "Dn1_A7") (pintype "unspecified"))
      (node (ref "USB1") (pin "B7") (pinfunction "Dn2_B7") (pintype "unspecified"))
    )
    (net (code "12") (name "CON_USB_P") (class "Default")
      (node (ref "D2") (pin "1") (pinfunction "1_1") (pintype "unspecified"))
      (node (ref "R3") (pin "2") (pinfunction "2_2") (pintype "input"))
      (node (ref "USB1") (pin "A6") (pinfunction "Dp1_A6") (pintype "unspecified"))
      (node (ref "USB1") (pin "B6") (pinfunction "Dp2_B6") (pintype "unspecified"))
    )
    (net (code "13") (name "ENC1") (class "Default")
      (node (ref "D15") (pin "2") (pinfunction "A_2") (pintype "unspecified"))
      (node (ref "SW13") (pin "2") (pinfunction "2_2") (pintype "unspecified"))
    )
    (net (code "14") (name "ENC1_A") (class "Default")
      (node (ref "C21") (pin "2") (pinfunction "2_2") (pintype "input"))
      (node (ref "R23") (pin "2") (pinfunction "2_2") (pintype "input"))
      (node (ref "U1") (pin "18") (pinfunction "GPIO15_18") (pintype "bidirectional"))
    )
    (net (code "15") (name "ENC1_B") (class "Default")
      (node (ref "C22") (pin "2") (pinfunction "2_2") (pintype "input"))
      (node (ref "R24") (pin "2") (pinfunction "2_2") (pintype "input"))
      (node (ref "U1") (pin "27") (pinfunction "GPIO16_27") (pintype "bidirectional"))
    )
    (net (code "16") (name "ENC2") (class "Default")
      (node (ref "D16") (pin "2") (pinfunction "A_2") (pintype "unspecified"))
      (node (ref "SW14") (pin "2") (pinfunction "2_2") (pintype "unspecified"))
    )
    (net (code "17") (name "ENC2_A") (class "Default")
      (node (ref "C24") (pin "2") (pinfunction "2_2") (pintype "input"))
      (node (ref "R28") (pin "2") (pinfunction "2_2") (pintype "input"))
      (node (ref "U1") (pin "28") (pinfunction "GPIO17_28") (pintype "bidirectional"))
    )
    (net (code "18") (name "ENC2_B") (class "Default")
      (node (ref "C25") (pin "2") (pinfunction "2_2") (pintype "input"))
      (node (ref "R29") (pin "2") (pinfunction "2_2") (pintype "input"))
      (node (ref "U1") (pin "29") (pinfunction "GPIO18_29") (pintype "bidirectional"))
    )
    (net (code "19") (name "ENC3") (class "Default")
      (node (ref "D17") (pin "2") (pinfunction "A_2") (pintype "unspecified"))
      (node (ref "SW15") (pin "2") (pinfunction "2_2") (pintype "unspecified"))
    )
    (net (code "20") (name "ENC3_A") (class "Default")
      (node (ref "C27") (pin "2") (pinfunction "2_2") (pintype "input"))
      (node (ref "R32") (pin "2") (pinfunction "2_2") (pintype "input"))
      (node (ref "U1") (pin "30") (pinfunction "GPIO19_30") (pintype "bidirectional"))
    )
    (net (code "21") (name "ENC3_B") (class "Default")
      (node (ref "C28") (pin "2") (pinfunction "2_2") (pintype "input"))
      (node (ref "R33") (pin "2") (pinfunction "2_2") (pintype "input"))
      (node (ref "U1") (pin "31") (pinfunction "GPIO20_31") (pintype "bidirectional"))
    )
    (net (code "22") (name "GND") (class "Default")
      (node (ref "C1") (pin "2") (pinfunction "2_2") (pintype "input"))
      (node (ref "C10") (pin "2") (pinfunction "2_2") (pintype "input"))
      (node (ref "C11") (pin "2") (pinfunction "2_2") (pintype "input"))
      (node (ref "C12") (pin "2") (pinfunction "2_2") (pintype "input"))
      (node (ref "C13") (pin "2") (pinfunction "2_2") (pintype "input"))
      (node (ref "C14") (pin "2") (pinfunction "2_2") (pintype "input"))
      (node (ref "C15") (pin "2") (pinfunction "2_2") (pintype "input"))
      (node (ref "C16") (pin "1") (pinfunction "1_1") (pintype "unspecified"))
      (node (ref "C17") (pin "2") (pinfunction "2_2") (pintype "unspecified"))
      (node (ref "C18") (pin "2") (pinfunction "2_2") (pintype "unspecified"))
      (node (ref "C19") (pin "2") (pinfunction "2_2") (pintype "input"))
      (node (ref "C2") (pin "2") (pinfunction "2_2") (pintype "input"))
      (node (ref "C20") (pin "1") (pinfunction "1_1") (pintype "input"))
      (node (ref "C21") (pin "1") (pinfunction "1_1") (pintype "input"))
      (node (ref "C22") (pin "1") (pinfunction "1_1") (pintype "input"))
      (node (ref "C23") (pin "2") (pinfunction "2_2") (pintype "input"))
      (node (ref "C24") (pin "1") (pinfunction "1_1") (pintype "input"))
      (node (ref "C25") (pin "1") (pinfunction "1_1") (pintype "input"))
      (node (ref "C26") (pin "2") (pinfunction "2_2") (pintype "input"))
      (node (ref "C27") (pin "1") (pinfunction "1_1") (pintype "input"))
      (node (ref "C28") (pin "1") (pinfunction "1_1") (pintype "input"))
      (node (ref "C29") (pin "2") (pinfunction "2_2") (pintype "input"))
      (node (ref "C3") (pin "2") (pinfunction "2_2") (pintype "input"))
      (node (ref "C31") (pin "2") (pinfunction "2_2") (pintype "input"))
      (node (ref "C32") (pin "2") (pinfunction "2_2") (pintype "input"))
      (node (ref "C33") (pin "2") (pinfunction "2_2") (pintype "input"))
      (node (ref "C34") (pin "2") (pinfunction "2_2") (pintype "input"))
      (node (ref "C35") (pin "2") (pinfunction "2_2") (pintype "input"))
      (node (ref "C36") (pin "2") (pinfunction "2_2") (pintype "input"))
      (node (ref "C37") (pin "2") (pinfunction "2_2") (pintype "input"))
      (node (ref "C38") (pin "2") (pinfunction "2_2") (pintype "input"))
      (node (ref "C39") (pin "2") (pinfunction "2_2") (pintype "input"))
      (node (ref "C4") (pin "2") (pinfunction "2_2") (pintype "input"))
      (node (ref "C40") (pin "1") (pinfunction "1_1") (pintype "input"))
      (node (ref "C41") (pin "2") (pinfunction "2_2") (pintype "input"))
      (node (ref "C42") (pin "1") (pinfunction "1_1") (pintype "input"))
      (node (ref "C5") (pin "1") (pinfunction "1_1") (pintype "input"))
      (node (ref "C6") (pin "1") (pinfunction "1_1") (pintype "input"))
      (node (ref "C7") (pin "1") (pinfunction "1_1") (pintype "input"))
      (node (ref "C8") (pin "2") (pinfunction "2_2") (pintype "input"))
      (node (ref "C9") (pin "2") (pinfunction "2_2") (pintype "input"))
      (node (ref "D2") (pin "2") (pinfunction "2_2") (pintype "unspecified"))
      (node (ref "D3") (pin "1") (pinfunction "1_1") (pintype "unspecified"))
      (node (ref "D4") (pin "1") (pinfunction "1_1") (pintype "unspecified"))
      (node (ref "D5") (pin "1") (pinfunction "1_1") (pintype "unspecified"))
      (node (ref "H1") (pin "2") (pinfunction "2_2") (pintype "input"))
      (node (ref "LED1") (pin "2") (pinfunction "-_2") (pintype "unspecified"))
      (node (ref "LED10") (pin "1") (pinfunction "GND_1") (pintype "unspecified"))
      (node (ref "LED11") (pin "1") (pinfunction "GND_1") (pintype "unspecified"))
      (node (ref "LED12") (pin "1") (pinfunction "GND_1") (pintype "unspecified"))
      (node (ref "LED2") (pin "2") (pinfunction "K_2") (pintype "unspecified"))
      (node (ref "LED4") (pin "1") (pinfunction "GND_1") (pintype "unspecified"))
      (node (ref "LED5") (pin "1") (pinfunction "GND_1") (pintype "unspecified"))
      (node (ref "LED6") (pin "1") (pinfunction "GND_1") (pintype "unspecified"))
      (node (ref "LED7") (pin "1") (pinfunction "GND_1") (pintype "unspecified"))
      (node (ref "LED8") (pin "1") (pinfunction "GND_1") (pintype "unspecified"))
      (node (ref "LED9") (pin "1") (pinfunction "GND_1") (pintype "unspecified"))
      (node (ref "R4") (pin "1") (pinfunction "1_1") (pintype "input"))
      (node (ref "R5") (pin "1") (pinfunction "1_1") (pintype "input"))
      (node (ref "SW1") (pin "1") (pinfunction "A_1") (pintype "unspecified"))
      (node (ref "SW1") (pin "2") (pinfunction "B_2") (pintype "unspecified"))
      (node (ref "SW13") (pin "3") (pinfunction "3_3") (pintype "unspecified"))
      (node (ref "SW13") (pin "4") (pinfunction "4_4") (pintype "unspecified"))
      (node (ref "SW13") (pin "C") (pinfunction "C_C") (pintype "unspecified"))
      (node (ref "SW14") (pin "3") (pinfunction "3_3") (pintype "unspecified"))
      (node (ref "SW14") (pin "4") (pinfunction "4_4") (pintype "unspecified"))
      (node (ref "SW14") (pin "C") (pinfunction "C_C") (pintype "unspecified"))
      (node (ref "SW15") (pin "3") (pinfunction "3_3") (pintype "unspecified"))
      (node (ref "SW15") (pin "4") (pinfunction "4_4") (pintype "unspecified"))
      (node (ref "SW15") (pin "C") (pinfunction "C_C") (pintype "unspecified"))
      (node (ref "SW2") (pin "1") (pinfunction "A_1") (pintype "unspecified"))
      (node (ref "SW2") (pin "2") (pinfunction "B_2") (pintype "unspecified"))
      (node (ref "U1") (pin "19") (pinfunction "TESTEN_19") (pintype "unspecified"))
      (node (ref "U1") (pin "57") (pinfunction "GND_57") (pintype "bidirectional"))
      (node (ref "U15") (pin "3") (pinfunction "GND_3") (pintype "unspecified"))
      (node (ref "U2") (pin "2") (pinfunction "GND_2") (pintype "unspecified"))
      (node (ref "U2") (pin "4") (pinfunction "GND_4") (pintype "unspecified"))
      (node (ref "U3") (pin "2") (pinfunction "GND_2") (pintype "input"))
      (node (ref "U3") (pin "4") (pinfunction "GND_4") (pintype "input"))
      (node (ref "U4") (pin "4") (pinfunction "GND_4") (pintype "unspecified"))
      (node (ref "USB1") (pin "13") (pinfunction "EH_13") (pintype "unspecified"))
      (node (ref "USB1") (pin "14") (pinfunction "EH_14") (pintype "unspecified"))
      (node (ref "USB1") (pin "A1B12") (pinfunction "GND_A1B12") (pintype "unspecified"))
      (node (ref "USB1") (pin "B1A12") (pinfunction "GND_B1A12") (pintype "unspecified"))
    )
    (net (code "23") (name "GPIO25") (class "Default")
      (node (ref "R10") (pin "1") (pinfunction "1_1") (pintype "input"))
      (node (ref "U1") (pin "37") (pinfunction "GPIO25_37") (pintype "bidirectional"))
    )
    (net (code "24") (name "LED0") (class "Default")
      (node (ref "LED4") (pin "2") (pinfunction "DIN_2") (pintype "unspecified"))
      (node (ref "U15") (pin "4") (pinfunction "Y_4") (pintype "unspecified"))
    )
    (net (code "25") (name "LED0_BUF") (class "Default")
      (node (ref "R34") (pin "1") (pinfunction "1_1") (pintype "input"))
      (node (ref "U15") (pin "1") (pinfunction "NC_1") (pintype "unspecified"))
      (node (ref "U15") (pin "2") (pinfunction "A_2") (pintype "unspecified"))
    )
    (net (code "26") (name "LED0_RES") (class "Default")
      (node (ref "R34") (pin "2") (pinfunction "2_2") (pintype "input"))
      (node (ref "U1") (pin "36") (pinfunction "GPIO24_36") (pintype "bidirectional"))
    )
    (net (code "27") (name "LED1") (class "Default")
      (node (ref "LED4") (pin "4") (pinfunction "DOUT_4") (pintype "unspecified"))
      (node (ref "LED5") (pin "2") (pinfunction "DIN_2") (pintype "unspecified"))
    )
    (net (code "28") (name "LED2") (class "Default")
      (node (ref "LED5") (pin "4") (pinfunction "DOUT_4") (pintype "unspecified"))
      (node (ref "LED6") (pin "2") (pinfunction "DIN_2") (pintype "unspecified"))
    )
    (net (code "29") (name "LED3") (class "Default")
      (node (ref "LED6") (pin "4") (pinfunction "DOUT_4") (pintype "unspecified"))
      (node (ref "LED7") (pin "2") (pinfunction "DIN_2") (pintype "unspecified"))
    )
    (net (code "30") (name "LED4") (class "Default")
      (node (ref "LED7") (pin "4") (pinfunction "DOUT_4") (pintype "unspecified"))
      (node (ref "LED8") (pin "2") (pinfunction "DIN_2") (pintype "unspecified"))
    )
    (net (code "31") (name "LED5") (class "Default")
      (node (ref "LED8") (pin "4") (pinfunction "DOUT_4") (pintype "unspecified"))
      (node (ref "LED9") (pin "2") (pinfunction "DIN_2") (pintype "unspecified"))
    )
    (net (code "32") (name "LED6") (class "Default")
      (node (ref "LED10") (pin "2") (pinfunction "DIN_2") (pintype "unspecified"))
      (node (ref "LED9") (pin "4") (pinfunction "DOUT_4") (pintype "unspecified"))
    )
    (net (code "33") (name "LED7") (class "Default")
      (node (ref "LED10") (pin "4") (pinfunction "DOUT_4") (pintype "unspecified"))
      (node (ref "LED11") (pin "2") (pinfunction "DIN_2") (pintype "unspecified"))
    )
    (net (code "34") (name "LED8") (class "Default")
      (node (ref "LED11") (pin "4") (pinfunction "DOUT_4") (pintype "unspecified"))
      (node (ref "LED12") (pin "2") (pinfunction "DIN_2") (pintype "unspecified"))
    )
    (net (code "35") (name "Net-(D6-A)") (class "Default")
      (node (ref "D6") (pin "2") (pinfunction "A_2") (pintype "unspecified"))
      (node (ref "U11") (pin "2") (pinfunction "2_2") (pintype "input"))
    )
    (net (code "36") (name "Net-(D7-A)") (class "Default")
      (node (ref "D7") (pin "2") (pinfunction "A_2") (pintype "unspecified"))
      (node (ref "U10") (pin "2") (pinfunction "2_2") (pintype "input"))
    )
    (net (code "37") (name "Net-(D8-A)") (class "Default")
      (node (ref "D8") (pin "2") (pinfunction "A_2") (pintype "unspecified"))
      (node (ref "U12") (pin "2") (pinfunction "2_2") (pintype "input"))
    )
    (net (code "38") (name "Net-(D9-A)") (class "Default")
      (node (ref "D9") (pin "2") (pinfunction "A_2") (pintype "unspecified"))
      (node (ref "U13") (pin "2") (pinfunction "2_2") (pintype "input"))
    )
    (net (code "39") (name "Net-(D10-A)") (class "Default")
      (node (ref "D10") (pin "2") (pinfunction "A_2") (pintype "unspecified"))
      (node (ref "U5") (pin "2") (pinfunction "2_2") (pintype "input"))
    )
    (net (code "40") (name "Net-(D11-A)") (class "Default")
      (node (ref "D11") (pin "2") (pinfunction "A_2") (pintype "unspecified"))
      (node (ref "U6") (pin "2") (pinfunction "2_2") (pintype "input"))
    )
    (net (code "41") (name "Net-(D12-A)") (class "Default")
      (node (ref "D12") (pin "2") (pinfunction "A_2") (pintype "unspecified"))
      (node (ref "U7") (pin "2") (pinfunction "2_2") (pintype "input"))
    )
    (net (code "42") (name "Net-(D13-A)") (class "Default")
      (node (ref "D13") (pin "2") (pinfunction "A_2") (pintype "unspecified"))
      (node (ref "U8") (pin "2") (pinfunction "2_2") (pintype "input"))
    )
    (net (code "43") (name "Net-(D14-A)") (class "Default")
      (node (ref "D14") (pin "2") (pinfunction "A_2") (pintype "unspecified"))
      (node (ref "U9") (pin "2") (pinfunction "2_2") (pintype "input"))
    )
    (net (code "44") (name "Net-(LED1-+)") (class "Default")
      (node (ref "LED1") (pin "1") (pinfunction "+_1") (pintype "unspecified"))
      (node (ref "R10") (pin "2") (pinfunction "2_2") (pintype "input"))
    )
    (net (code "45") (name "Net-(LED2-A)") (class "Default")
      (node (ref "LED2") (pin "1") (pinfunction "A_1") (pintype "unspecified"))
      (node (ref "R11") (pin "2") (pinfunction "2_2") (pintype "input"))
    )
    (net (code "46") (name "Net-(LED13---Pad2)") (class "Default")
      (node (ref "LED13") (pin "2") (pinfunction "-_2") (pintype "unspecified"))
      (node (ref "R36") (pin "2") (pinfunction "2_2") (pintype "input"))
    )
    (net (code "47") (name "Net-(LED13---Pad3)") (class "Default")
      (node (ref "LED13") (pin "3") (pinfunction "-_3") (pintype "unspecified"))
      (node (ref "R37") (pin "2") (pinfunction "2_2") (pintype "input"))
    )
    (net (code "48") (name "Net-(LED13---Pad4)") (class "Default")
      (node (ref "LED13") (pin "4") (pinfunction "-_4") (pintype "unspecified"))
      (node (ref "R38") (pin "2") (pinfunction "2_2") (pintype "input"))
    )
    (net (code "49") (name "Net-(R21-Pad2)") (class "Default")
      (node (ref "R21") (pin "2") (pinfunction "2_2") (pintype "input"))
      (node (ref "R23") (pin "1") (pinfunction "1_1") (pintype "input"))
      (node (ref "SW13") (pin "A") (pinfunction "A_A") (pintype "unspecified"))
    )
    (net (code "50") (name "Net-(R22-Pad2)") (class "Default")
      (node (ref "R22") (pin "2") (pinfunction "2_2") (pintype "input"))
      (node (ref "R24") (pin "1") (pinfunction "1_1") (pintype "input"))
      (node (ref "SW13") (pin "B") (pinfunction "B_B") (pintype "unspecified"))
    )
    (net (code "51") (name "Net-(R26-Pad2)") (class "Default")
      (node (ref "R26") (pin "2") (pinfunction "2_2") (pintype "input"))
      (node (ref "R28") (pin "1") (pinfunction "1_1") (pintype "input"))
      (node (ref "SW14") (pin "A") (pinfunction "A_A") (pintype "unspecified"))
    )
    (net (code "52") (name "Net-(R27-Pad2)") (class "Default")
      (node (ref "R27") (pin "2") (pinfunction "2_2") (pintype "input"))
      (node (ref "R29") (pin "1") (pinfunction "1_1") (pintype "input"))
      (node (ref "SW14") (pin "B") (pinfunction "B_B") (pintype "unspecified"))
    )
    (net (code "53") (name "Net-(R30-Pad2)") (class "Default")
      (node (ref "R30") (pin "2") (pinfunction "2_2") (pintype "input"))
      (node (ref "R32") (pin "1") (pinfunction "1_1") (pintype "input"))
      (node (ref "SW15") (pin "A") (pinfunction "A_A") (pintype "unspecified"))
    )
    (net (code "54") (name "Net-(R31-Pad2)") (class "Default")
      (node (ref "R31") (pin "2") (pinfunction "2_2") (pintype "input"))
      (node (ref "R33") (pin "1") (pinfunction "1_1") (pintype "input"))
      (node (ref "SW15") (pin "B") (pinfunction "B_B") (pintype "unspecified"))
    )
    (net (code "55") (name "Net-(SW1-C)") (class "Default")
      (node (ref "NFR8") (pin "1") (pinfunction "1_1") (pintype "input"))
      (node (ref "R7") (pin "1") (pinfunction "1_1") (pintype "input"))
      (node (ref "SW1") (pin "3") (pinfunction "C_3") (pintype "unspecified"))
      (node (ref "SW1") (pin "4") (pinfunction "D_4") (pintype "unspecified"))
    )
    (net (code "56") (name "Net-(SW2-C)") (class "Default")
      (node (ref "R8") (pin "1") (pinfunction "1_1") (pintype "input"))
      (node (ref "R9") (pin "1") (pinfunction "1_1") (pintype "input"))
      (node (ref "SW2") (pin "3") (pinfunction "C_3") (pintype "unspecified"))
      (node (ref "SW2") (pin "4") (pinfunction "D_4") (pintype "unspecified"))
    )
    (net (code "57") (name "Net-(USB1-CC1)") (class "Default")
      (node (ref "R5") (pin "2") (pinfunction "2_2") (pintype "input"))
      (node (ref "USB1") (pin "A5") (pinfunction "CC1_A5") (pintype "unspecified"))
    )
    (net (code "58") (name "Net-(USB1-CC2)") (class "Default")
      (node (ref "R4") (pin "2") (pinfunction "2_2") (pintype "input"))
      (node (ref "USB1") (pin "B5") (pinfunction "CC2_B5") (pintype "unspecified"))
    )
    (net (code "59") (name "QSPI_SCLK") (class "Default")
      (node (ref "U1") (pin "52") (pinfunction "QSPI_SCLK_52") (pintype "output"))
      (node (ref "U4") (pin "6") (pinfunction "CLK_6") (pintype "unspecified"))
    )
    (net (code "60") (name "QSPI_SD0") (class "Default")
      (node (ref "U1") (pin "53") (pinfunction "QSPI_SD0_53") (pintype "bidirectional"))
      (node (ref "U4") (pin "5") (pinfunction "DI_5") (pintype "unspecified"))
    )
    (net (code "61") (name "QSPI_SD1") (class "Default")
      (node (ref "U1") (pin "55") (pinfunction "QSPI_SD1_55") (pintype "bidirectional"))
      (node (ref "U4") (pin "2") (pinfunction "DO_2") (pintype "unspecified"))
    )
    (net (code "62") (name "QSPI_SD2") (class "Default")
      (node (ref "U1") (pin "54") (pinfunction "QSPI_SD2_54") (pintype "bidirectional"))
      (node (ref "U4") (pin "3") (pinfunction "IO2_3") (pintype "unspecified"))
    )
    (net (code "63") (name "QSPI_SD3") (class "Default")
      (node (ref "U1") (pin "51") (pinfunction "QSPI_SD3_51") (pintype "bidirectional"))
      (node (ref "U4") (pin "7") (pinfunction "IO3_7") (pintype "unspecified"))
    )
    (net (code "64") (name "QSPI_SS") (class "Default")
      (node (ref "R7") (pin "2") (pinfunction "2_2") (pintype "input"))
      (node (ref "U1") (pin "56") (pinfunction "QSPI_SS_56") (pintype "bidirectional"))
      (node (ref "U4") (pin "1") (pinfunction "CS#_1") (pintype "unspecified"))
    )
    (net (code "65") (name "RESETN") (class "Default")
      (node (ref "C20") (pin "2") (pinfunction "2_2") (pintype "input"))
      (node (ref "R9") (pin "2") (pinfunction "2_2") (pintype "input"))
      (node (ref "U1") (pin "26") (pinfunction "RUN_26") (pintype "input"))
    )
    (net (code "66") (name "ROW0") (class "Default")
      (node (ref "D6") (pin "1") (pinfunction "K_1") (pintype "unspecified"))
      (node (ref "D7") (pin "1") (pinfunction "K_1") (pintype "unspecified"))
      (node (ref "D8") (pin "1") (pinfunction "K_1") (pintype "unspecified"))
      (node (ref "R18") (pin "2") (pinfunction "2_2") (pintype "input"))
    )
    (net (code "67") (name "ROW0_R") (class "Default")
      (node (ref "R18") (pin "1") (pinfunction "1_1") (pintype "input"))
      (node (ref "U1") (pin "11") (pinfunction "GPIO8_11") (pintype "bidirectional"))
    )
    (net (code "68") (name "ROW1") (class "Default")
      (node (ref "D10") (pin "1") (pinfunction "K_1") (pintype "unspecified"))
      (node (ref "D11") (pin "1") (pinfunction "K_1") (pintype "unspecified"))
      (node (ref "D9") (pin "1") (pinfunction "K_1") (pintype "unspecified"))
      (node (ref "R19") (pin "2") (pinfunction "2_2") (pintype "input"))
    )
    (net (code "69") (name "ROW1_R") (class "Default")
      (node (ref "R19") (pin "1") (pinfunction "1_1") (pintype "input"))
      (node (ref "U1") (pin "12") (pinfunction "GPIO9_12") (pintype "bidirectional"))
    )
    (net (code "70") (name "ROW2") (class "Default")
      (node (ref "D12") (pin "1") (pinfunction "K_1") (pintype "unspecified"))
      (node (ref "D13") (pin "1") (pinfunction "K_1") (pintype "unspecified"))
      (node (ref "D14") (pin "1") (pinfunction "K_1") (pintype "unspecified"))
      (node (ref "R20") (pin "2") (pinfunction "2_2") (pintype "input"))
    )
    (net (code "71") (name "ROW2_R") (class "Default")
      (node (ref "R20") (pin "1") (pinfunction "1_1") (pintype "input"))
      (node (ref "U1") (pin "13") (pinfunction "GPIO10_13") (pintype "bidirectional"))
    )
    (net (code "72") (name "ROW3") (class "Default")
      (node (ref "D15") (pin "1") (pinfunction "K_1") (pintype "unspecified"))
      (node (ref "D16") (pin "1") (pinfunction "K_1") (pintype "unspecified"))
      (node (ref "D17") (pin "1") (pinfunction "K_1") (pintype "unspecified"))
      (node (ref "R25") (pin "2") (pinfunction "2_2") (pintype "input"))
    )
    (net (code "73") (name "ROW3_R") (class "Default")
      (node (ref "R25") (pin "1") (pinfunction "1_1") (pintype "input"))
      (node (ref "U1") (pin "14") (pinfunction "GPIO11_14") (pintype "bidirectional"))
    )
    (net (code "74") (name "SWCLK") (class "Default")
      (node (ref "H1") (pin "3") (pinfunction "3_3") (pintype "input"))
      (node (ref "U1") (pin "24") (pinfunction "SWCLK_24") (pintype "output"))
    )
    (net (code "75") (name "SWDIO") (class "Default")
      (node (ref "H1") (pin "1") (pinfunction "1_1") (pintype "input"))
      (node (ref "U1") (pin "25") (pinfunction "SWD_25") (pintype "bidirectional"))
    )
    (net (code "76") (name "USBN") (class "Default")
      (node (ref "R2") (pin "1") (pinfunction "1_1") (pintype "input"))
      (node (ref "U1") (pin "46") (pinfunction "USB_DM_46") (pintype "bidirectional"))
    )
    (net (code "77") (name "USBP") (class "Default")
      (node (ref "R3") (pin "1") (pinfunction "1_1") (pintype "input"))
      (node (ref "U1") (pin "47") (pinfunction "USB_DP_47") (pintype "bidirectional"))
    )
    (net (code "78") (name "USB_5V") (class "Default")
      (node (ref "C13") (pin "1") (pinfunction "1_1") (pintype "input"))
      (node (ref "C14") (pin "1") (pinfunction "1_1") (pintype "input"))
      (node (ref "C15") (pin "1") (pinfunction "1_1") (pintype "input"))
      (node (ref "C40") (pin "2") (pinfunction "2_2") (pintype "input"))
      (node (ref "D4") (pin "2") (pinfunction "2_2") (pintype "unspecified"))
      (node (ref "D5") (pin "2") (pinfunction "2_2") (pintype "unspecified"))
      (node (ref "R35") (pin "1") (pinfunction "1_1") (pintype "input"))
      (node (ref "U15") (pin "5") (pinfunction "VCC_5") (pintype "unspecified"))
      (node (ref "U2") (pin "1") (pinfunction "IN_1") (pintype "unspecified"))
      (node (ref "USB1") (pin "A4B9") (pinfunction "VBUS_A4B9") (pintype "unspecified"))
      (node (ref "USB1") (pin "B4A9") (pinfunction "VBUS_B4A9") (pintype "unspecified"))
    )
    (net (code "79") (name "USER_LED2_B") (class "Default")
      (node (ref "R38") (pin "1") (pinfunction "1_1") (pintype "input"))
      (node (ref "U1") (pin "40") (pinfunction "GPIO28_ADC2_40") (pintype "bidirectional"))
    )
    (net (code "80") (name "USER_LED2_G") (class "Default")
      (node (ref "R37") (pin "1") (pinfunction "1_1") (pintype "input"))
      (node (ref "U1") (pin "39") (pinfunction "GPIO27_ADC1_39") (pintype "bidirectional"))
    )
    (net (code "81") (name "USER_LED2_R") (class "Default")
      (node (ref "R36") (pin "1") (pinfunction "1_1") (pintype "input"))
      (node (ref "U1") (pin "38") (pinfunction "GPIO26_ADC0_38") (pintype "bidirectional"))
    )
    (net (code "82") (name "XIN") (class "Default")
      (node (ref "C17") (pin "1") (pinfunction "1_1") (pintype "unspecified"))
      (node (ref "R7NF") (pin "2") (pinfunction "2_2") (pintype "input"))
      (node (ref "U1") (pin "20") (pinfunction "XIN_20") (pintype "input"))
      (node (ref "U3") (pin "1") (pinfunction "1_1") (pintype "input"))
    )
    (net (code "83") (name "XOUT") (class "Default")
      (node (ref "R6") (pin "1") (pinfunction "1_1") (pintype "input"))
      (node (ref "R7NF") (pin "1") (pinfunction "1_1") (pintype "input"))
      (node (ref "U1") (pin "21") (pinfunction "XOUT_21") (pintype "unspecified"))
    )
    (net (code "84") (name "X_R") (class "Default")
      (node (ref "C18") (pin "1") (pinfunction "1_1") (pintype "unspecified"))
      (node (ref "R6") (pin "2") (pinfunction "2_2") (pintype "input"))
      (node (ref "U3") (pin "3") (pinfunction "3_3") (pintype "input"))
    )
    (net (code "85") (name "unconnected-(LED12-DOUT-Pad4)") (class "Default")
      (node (ref "LED12") (pin "4") (pinfunction "DOUT_4") (pintype "unspecified+no_connect"))
    )
    (net (code "86") (name "unconnected-(U1-GPIO3-Pad5)") (class "Default")
      (node (ref "U1") (pin "5") (pinfunction "GPIO3_5") (pintype "bidirectional+no_connect"))
    )
    (net (code "87") (name "unconnected-(U1-GPIO4-Pad6)") (class "Default")
      (node (ref "U1") (pin "6") (pinfunction "GPIO4_6") (pintype "bidirectional+no_connect"))
    )
    (net (code "88") (name "unconnected-(U1-GPIO5-Pad7)") (class "Default")
      (node (ref "U1") (pin "7") (pinfunction "GPIO5_7") (pintype "bidirectional+no_connect"))
    )
    (net (code "89") (name "unconnected-(U1-GPIO6-Pad8)") (class "Default")
      (node (ref "U1") (pin "8") (pinfunction "GPIO6_8") (pintype "bidirectional+no_connect"))
    )
    (net (code "90") (name "unconnected-(U1-GPIO7-Pad9)") (class "Default")
      (node (ref "U1") (pin "9") (pinfunction "GPIO7_9") (pintype "bidirectional+no_connect"))
    )
    (net (code "91") (name "unconnected-(U1-GPIO12-Pad15)") (class "Default")
      (node (ref "U1") (pin "15") (pinfunction "GPIO12_15") (pintype "bidirectional+no_connect"))
    )
    (net (code "92") (name "unconnected-(U1-GPIO13-Pad16)") (class "Default")
      (node (ref "U1") (pin "16") (pinfunction "GPIO13_16") (pintype "bidirectional+no_connect"))
    )
    (net (code "93") (name "unconnected-(U1-GPIO14-Pad17)") (class "Default")
      (node (ref "U1") (pin "17") (pinfunction "GPIO14_17") (pintype "bidirectional+no_connect"))
    )
    (net (code "94") (name "unconnected-(U1-GPIO21-Pad32)") (class "Default")
      (node (ref "U1") (pin "32") (pinfunction "GPIO21_32") (pintype "bidirectional+no_connect"))
    )
    (net (code "95") (name "unconnected-(U1-GPIO22-Pad34)") (class "Default")
      (node (ref "U1") (pin "34") (pinfunction "GPIO22_34") (pintype "bidirectional+no_connect"))
    )
    (net (code "96") (name "unconnected-(U1-GPIO23-Pad35)") (class "Default")
      (node (ref "U1") (pin "35") (pinfunction "GPIO23_35") (pintype "bidirectional+no_connect"))
    )
    (net (code "97") (name "unconnected-(U1-GPIO29_ADC3-Pad41)") (class "Default")
      (node (ref "U1") (pin "41") (pinfunction "GPIO29_ADC3_41") (pintype "bidirectional+no_connect"))
    )
    (net (code "98") (name "unconnected-(USB1-SBU1-PadA8)") (class "Default")
      (node (ref "USB1") (pin "A8") (pinfunction "SBU1_A8") (pintype "unspecified+no_connect"))
    )
    (net (code "99") (name "unconnected-(USB1-SBU2-PadB8)") (class "Default")
      (node (ref "USB1") (pin "B8") (pinfunction "SBU2_B8") (pintype "unspecified+no_connect"))
    )
  )
)
